# SparkFun_MMA8452Q-Breakout.net
KiCad netlist of a schematic drawn in EAGLE
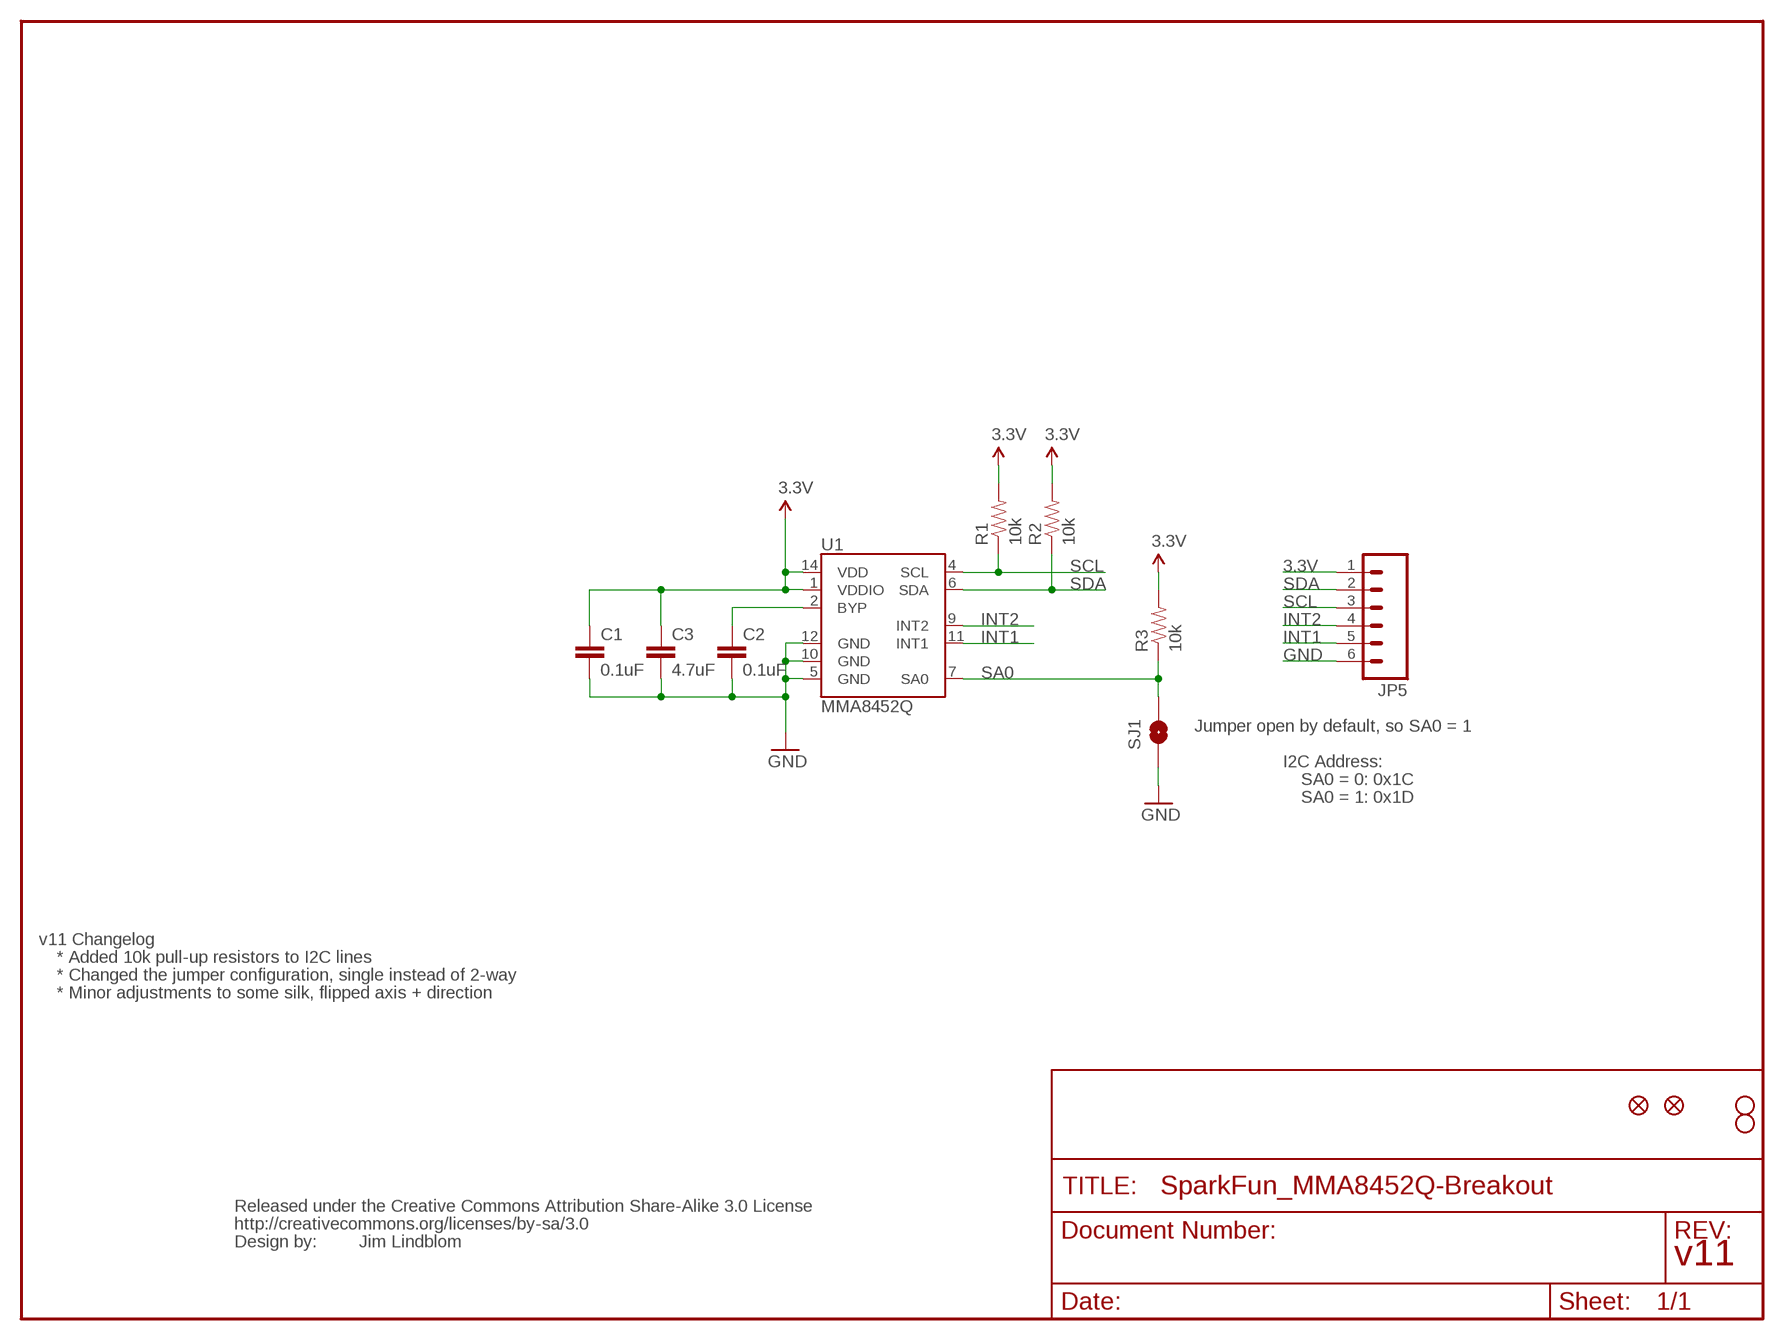
[diagram p0: schematic, sheet 1]

(export (version "E")
  (design (tool "Eeschema 10.0.6"))
  (components
    (comp (ref "C1")
      (value "0.1uF")
      (footprint "eagle-import:0402-CAP")
      (libsource (lib "eagle-import") (part "CAP0402-CAP"))
    )
    (comp (ref "C2")
      (value "0.1uF")
      (footprint "eagle-import:0402-CAP")
      (libsource (lib "eagle-import") (part "CAP0402-CAP"))
    )
    (comp (ref "C3")
      (value "4.7uF")
      (footprint "eagle-import:0402-CAP")
      (libsource (lib "eagle-import") (part "CAP0402-CAP"))
    )
    (comp (ref "JP2")
      (value "FIDUCIALUFIDUCIAL")
      (footprint "eagle-import:MICRO-FIDUCIAL")
      (libsource (lib "eagle-import") (part "FIDUCIALUFIDUCIAL"))
    )
    (comp (ref "JP3")
      (value "STAND-OFF")
      (footprint "eagle-import:STAND-OFF")
      (libsource (lib "eagle-import") (part "STAND-OFF"))
    )
    (comp (ref "JP4")
      (value "STAND-OFF")
      (footprint "eagle-import:STAND-OFF")
      (libsource (lib "eagle-import") (part "STAND-OFF"))
    )
    (comp (ref "JP5")
      (value "M06SIP")
      (footprint "eagle-import:1X06")
      (libsource (lib "eagle-import") (part "M06SIP"))
    )
    (comp (ref "JP6")
      (value "FIDUCIALUFIDUCIAL")
      (footprint "eagle-import:MICRO-FIDUCIAL")
      (libsource (lib "eagle-import") (part "FIDUCIALUFIDUCIAL"))
    )
    (comp (ref "R1")
      (value "10k")
      (footprint "eagle-import:0402-RES")
      (libsource (lib "eagle-import") (part "RESISTOR0402-RES"))
    )
    (comp (ref "R2")
      (value "10k")
      (footprint "eagle-import:0402-RES")
      (libsource (lib "eagle-import") (part "RESISTOR0402-RES"))
    )
    (comp (ref "R3")
      (value "10k")
      (footprint "eagle-import:0402-RES")
      (libsource (lib "eagle-import") (part "RESISTOR0402-RES"))
    )
    (comp (ref "SJ1")
      (value "SOLDERJUMPERNO")
      (footprint "eagle-import:SJ_2S-NO")
      (libsource (lib "eagle-import") (part "SOLDERJUMPERNO"))
    )
    (comp (ref "U$2")
      (value "CREATIVE_COMMONS")
      (footprint "eagle-import:CREATIVE_COMMONS")
      (libsource (lib "eagle-import") (part "CREATIVE_COMMONS"))
    )
    (comp (ref "U1")
      (value "MMA8452Q")
      (footprint "eagle-import:QFN-16_0.5MM")
      (libsource (lib "eagle-import") (part "MMA8452Q"))
    )
  )
  (nets
    (net (code "1") (name "/INT1") (class "Default")
      (node (ref "JP5") (pin "5") (pinfunction "5_5") (pintype "passive"))
      (node (ref "U1") (pin "11") (pinfunction "INT1_11") (pintype "bidirectional"))
    )
    (net (code "2") (name "/INT2") (class "Default")
      (node (ref "JP5") (pin "4") (pinfunction "4_4") (pintype "passive"))
      (node (ref "U1") (pin "9") (pinfunction "INT2_9") (pintype "bidirectional"))
    )
    (net (code "3") (name "/SA0") (class "Default")
      (node (ref "R3") (pin "1") (pinfunction "1_1") (pintype "passive"))
      (node (ref "SJ1") (pin "2") (pinfunction "2_2") (pintype "passive"))
      (node (ref "U1") (pin "7") (pinfunction "SA0_7") (pintype "bidirectional"))
    )
    (net (code "4") (name "/SCL") (class "Default")
      (node (ref "JP5") (pin "3") (pinfunction "3_3") (pintype "passive"))
      (node (ref "R1") (pin "1") (pinfunction "1_1") (pintype "passive"))
      (node (ref "U1") (pin "4") (pinfunction "SCL_4") (pintype "bidirectional"))
    )
    (net (code "5") (name "/SDA") (class "Default")
      (node (ref "JP5") (pin "2") (pinfunction "2_2") (pintype "passive"))
      (node (ref "R2") (pin "1") (pinfunction "1_1") (pintype "passive"))
      (node (ref "U1") (pin "6") (pinfunction "SDA_6") (pintype "bidirectional"))
    )
    (net (code "6") (name "3.3V") (class "Default")
      (node (ref "C1") (pin "1") (pinfunction "1_1") (pintype "passive"))
      (node (ref "C3") (pin "1") (pinfunction "1_1") (pintype "passive"))
      (node (ref "JP5") (pin "1") (pinfunction "1_1") (pintype "passive"))
      (node (ref "R1") (pin "2") (pinfunction "2_2") (pintype "passive"))
      (node (ref "R2") (pin "2") (pinfunction "2_2") (pintype "passive"))
      (node (ref "R3") (pin "2") (pinfunction "2_2") (pintype "passive"))
      (node (ref "U1") (pin "1") (pinfunction "VDDIO_1") (pintype "bidirectional"))
      (node (ref "U1") (pin "14") (pinfunction "VDD_14") (pintype "bidirectional"))
    )
    (net (code "7") (name "GND") (class "Default")
      (node (ref "C1") (pin "2") (pinfunction "2_2") (pintype "passive"))
      (node (ref "C2") (pin "2") (pinfunction "2_2") (pintype "passive"))
      (node (ref "C3") (pin "2") (pinfunction "2_2") (pintype "passive"))
      (node (ref "JP5") (pin "6") (pinfunction "6_6") (pintype "passive"))
      (node (ref "SJ1") (pin "1") (pinfunction "1_1") (pintype "passive"))
      (node (ref "U1") (pin "10") (pinfunction "GND_10") (pintype "bidirectional"))
      (node (ref "U1") (pin "12") (pinfunction "GND_12") (pintype "bidirectional"))
      (node (ref "U1") (pin "5") (pinfunction "GND_5") (pintype "bidirectional"))
    )
    (net (code "8") (name "Net-(U1-BYP)") (class "Default")
      (node (ref "C2") (pin "1") (pinfunction "1_1") (pintype "passive"))
      (node (ref "U1") (pin "2") (pinfunction "BYP_2") (pintype "bidirectional"))
    )
  )
)
